# Schematic_Rev2.net
KiCad netlist of a schematic drawn in Altium Designer
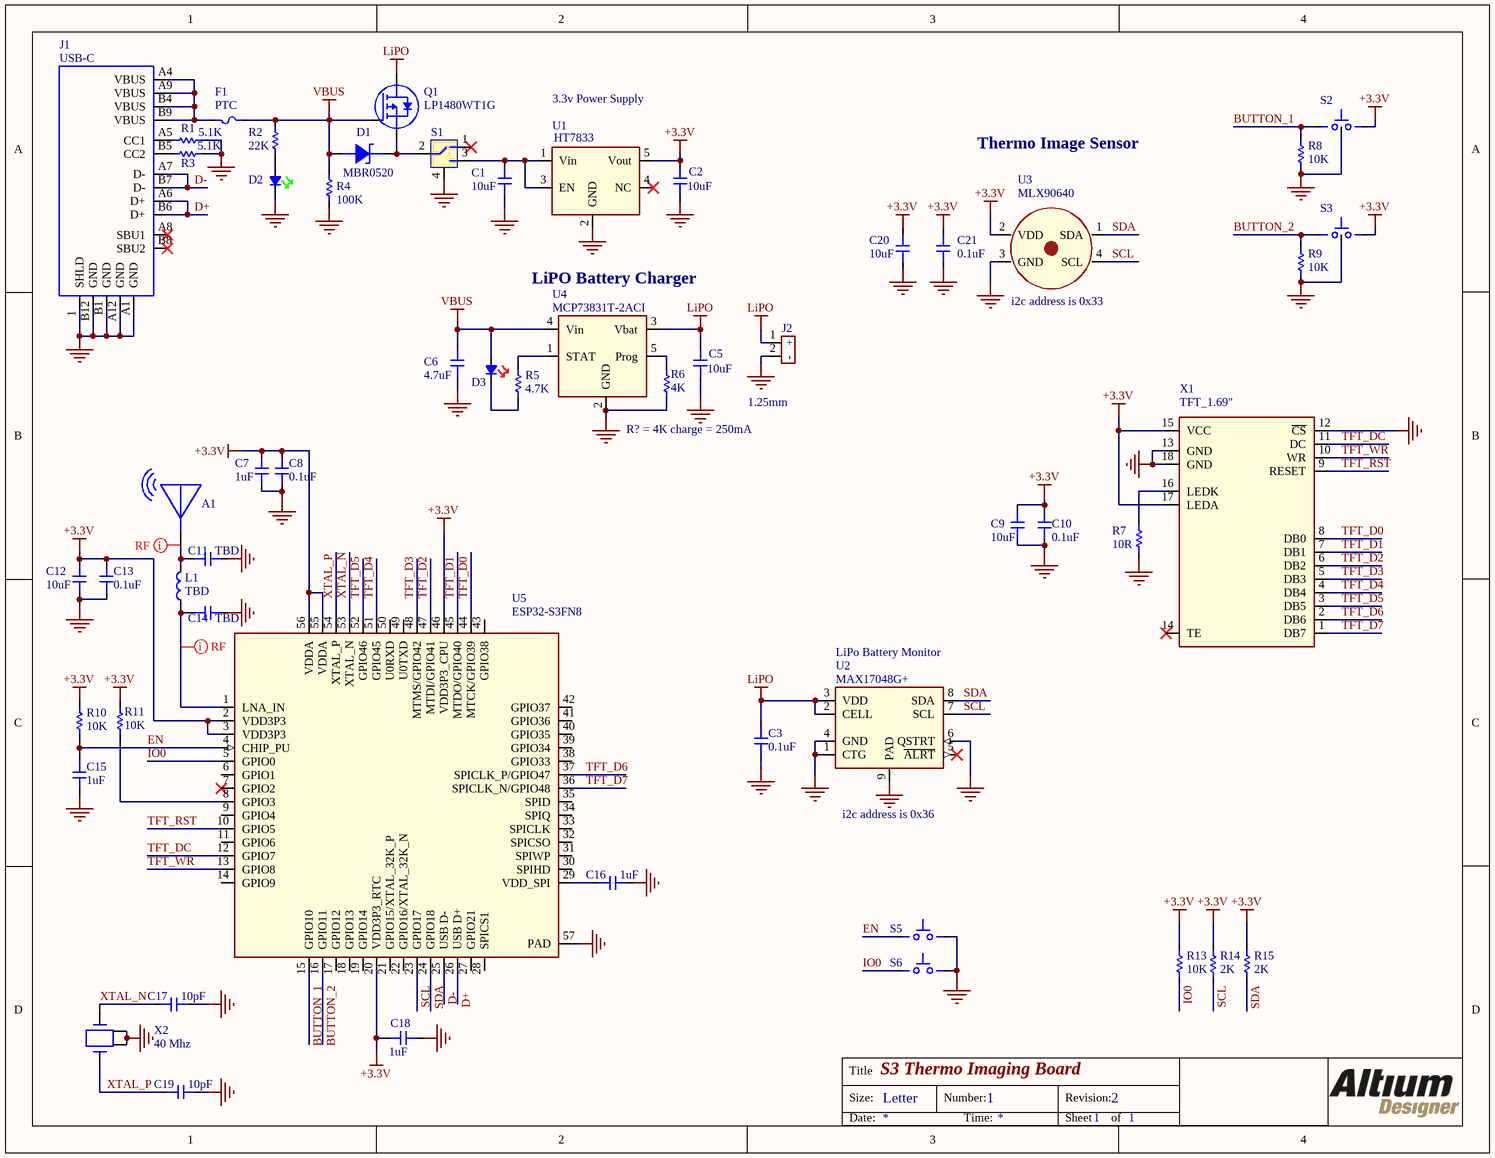
[diagram p0: Schematic_Rev2.SchDoc]

(export (version "E")
  (design (tool "Eeschema 10.0.6"))
  (components
    (comp (ref "A1")
      (value "ANT3216LL00R2400A")
      (footprint "ANT3216LL00R2400A")
      (description "Antenna Chip 2.4Gig")
      (fields (field (name "MANUFACTURER") "YAGEO"))
      (libsource (lib "MAR") (part "ANT3216LL00R2400A"))
    )
    (comp (ref "C1")
      (value "10uF")
      (footprint "CAPC2012X140N")
      (description "CAP 10uF 50V 0805")
      (libsource (lib "MAR") (part "CAP_0805"))
    )
    (comp (ref "C2")
      (value "10uF")
      (footprint "CAPC2012X140N")
      (description "CAP 10uF 50V 0805")
      (libsource (lib "MAR") (part "CAP_0805"))
    )
    (comp (ref "C3")
      (value "0.1uF")
      (footprint "CAPC1005X56N")
      (description "CAP 0.1uF 0402")
      (libsource (lib "MAR") (part "CAP_0402"))
    )
    (comp (ref "C5")
      (value "10uF")
      (footprint "CAPC2012X140N")
      (description "CAP 10uF 50V 0805")
      (libsource (lib "MAR") (part "CAP_0805"))
    )
    (comp (ref "C6")
      (value "4.7uF")
      (footprint "CAPC2012X140N")
      (description "CAP 4.7uF 0805")
      (libsource (lib "MAR") (part "CAP_0805"))
    )
    (comp (ref "C7")
      (value "1uF")
      (footprint "CAPC1608X09L")
      (description "CAP 1uF 0603")
      (libsource (lib "MAR") (part "CAP_0603"))
    )
    (comp (ref "C8")
      (value "0.1uF")
      (footprint "CAPC1608X09L")
      (description "CAP 0.1uF 0603")
      (libsource (lib "MAR") (part "CAP_0603"))
    )
    (comp (ref "C9")
      (value "10uF")
      (footprint "CAPC2012X140N")
      (description "CAP 10uF 0805")
      (libsource (lib "MAR") (part "CAP_0805"))
    )
    (comp (ref "C10")
      (value "0.1uF")
      (footprint "CAPC1608X09L")
      (description "CAP 0.1uF 0603")
      (libsource (lib "MAR") (part "CAP_0603"))
    )
    (comp (ref "C11")
      (value "TBD")
      (footprint "CAPC1005X56N")
      (description "CAP TBD 0402")
      (libsource (lib "MAR") (part "CAP_0402"))
    )
    (comp (ref "C12")
      (value "10uF")
      (footprint "CAPC2012X140N")
      (description "CAP 10uF 50V 0805")
      (libsource (lib "MAR") (part "CAP_0805"))
    )
    (comp (ref "C13")
      (value "0.1uF")
      (footprint "CAPC1005X56N")
      (description "CAP 0.1uF 0402")
      (libsource (lib "MAR") (part "CAP_0402"))
    )
    (comp (ref "C14")
      (value "TBD")
      (footprint "CAPC1005X56N")
      (description "CAP 0402")
      (libsource (lib "MAR") (part "CAP_0402"))
    )
    (comp (ref "C15")
      (value "1uF")
      (footprint "CAPC1005X56N")
      (description "CAP 1uF 0402")
      (libsource (lib "MAR") (part "CAP_0402"))
    )
    (comp (ref "C16")
      (value "1uF")
      (footprint "CAPC1005X56N")
      (description "CAP 1uF 0402")
      (libsource (lib "MAR") (part "CAP_0402"))
    )
    (comp (ref "C17")
      (value "10pF")
      (footprint "CAPC1005X56N")
      (description "CAP 10pF 0402")
      (libsource (lib "MAR") (part "CAP_0402"))
    )
    (comp (ref "C18")
      (value "1uF")
      (footprint "CAPC1608X09L")
      (description "CAP 1uF 0603")
      (libsource (lib "MAR") (part "CAP_0603"))
    )
    (comp (ref "C19")
      (value "10pF")
      (footprint "CAPC1005X56N")
      (description "CAP 10pF 0402")
      (libsource (lib "MAR") (part "CAP_0402"))
    )
    (comp (ref "C20")
      (value "10uF")
      (footprint "CAPC2012X140N")
      (description "CAP 10uF 50V 0805")
      (libsource (lib "MAR") (part "CAP_0805"))
    )
    (comp (ref "C21")
      (value "0.1uF")
      (footprint "CAPC1608X09L")
      (description "CAP 0.1uF 0603")
      (libsource (lib "MAR") (part "CAP_0603"))
    )
    (comp (ref "D1")
      (value "MBR0520")
      (footprint "SOD123")
      (description "DIODE SCHOTTKY 20V 500MA SOD-123")
      (fields (field (name "MANUFACTURER") "Micro") (field (name "PART_NUMBER") "C78746"))
      (libsource (lib "MAR") (part "MBR0520-TP"))
    )
    (comp (ref "D2")
      (value "Green Led")
      (footprint "LED1005X40N-Green")
      (description "LED Green 0402")
      (fields (field (name "PART_NUMBER") "C74338"))
      (libsource (lib "MAR") (part "LED_0402_SMALL_GREEN"))
    )
    (comp (ref "D3")
      (value "Red Led")
      (footprint "LED1005X40N-Red")
      (description "LED Red 0402")
      (fields (field (name "PART_NUMBER") "C364556") (field (name "MANUFACTURER") "Lite-On"))
      (libsource (lib "MAR") (part "LED_0402_SMALL_Red"))
    )
    (comp (ref "F1")
      (value "PTC")
      (footprint "RESC1608X06L (0603 FOOTPRINT)")
      (description "PTC FUSE 0.5mA hold, 1A trip 0603")
      (fields (field (name "MANUFACTURER") "JDT Fuse") (field (name "PART_NUMBER") "C2982257"))
      (libsource (lib "MAR") (part "PTC_FUSE_0603"))
    )
    (comp (ref "J1")
      (value "USB-C")
      (footprint "TYPE-C-31-M-12")
      (description "CONN RECPT USB-C")
      (fields (field (name "MANUFACTURER") "KHE") (field (name "PART_NUMBER") "C165948"))
      (libsource (lib "MAR") (part "USB-C"))
    )
    (comp (ref "J2")
      (value "1.5mm")
      (footprint "0530470260")
      (description "MIcro Conn 2POS 1.25mm Pitch Vertical")
      (fields (field (name "PART_NUMBER") "0530470260") (field (name "MANUFACTURER") "Molex"))
      (libsource (lib "MAR") (part "Molex_onn_2Pin_1.25mm_Vert"))
    )
    (comp (ref "L1")
      (value "TBD")
      (footprint "INDC1005X40L")
      (description "Inductor TBD")
      (libsource (lib "MAR") (part "Inductor"))
    )
    (comp (ref "Q1")
      (value "LP1480WT1G")
      (footprint "SC-70")
      (description "MOSFET P-CH 20V 1.4A SC-70")
      (fields (field (name "MANUFACTURER") "LRC") (field (name "PART_NUMBER") "C172434"))
      (libsource (lib "MAR") (part "LP1480WT1G"))
    )
    (comp (ref "R1")
      (value "5.1K")
      (footprint "RESC1005X40L (0402 FOOTPRINT)")
      (description "RES 5.1K 0402")
      (libsource (lib "MAR") (part "RES_0402"))
    )
    (comp (ref "R2")
      (value "22K")
      (footprint "RESC1005X40L (0402 FOOTPRINT)")
      (description "RES 22K 0402")
      (libsource (lib "MAR") (part "RES_0402"))
    )
    (comp (ref "R3")
      (value "5.1K")
      (footprint "RESC1005X40L (0402 FOOTPRINT)")
      (description "RES 5.1K 0402")
      (libsource (lib "MAR") (part "RES_0402"))
    )
    (comp (ref "R4")
      (value "100K")
      (footprint "RESC1005X40L (0402 FOOTPRINT)")
      (description "RES 100K 0402")
      (libsource (lib "MAR") (part "RES_0402"))
    )
    (comp (ref "R5")
      (value "4.7K")
      (footprint "RESC1005X40L (0402 FOOTPRINT)")
      (description "RES 4.7K 0402")
      (libsource (lib "MAR") (part "RES_0402"))
    )
    (comp (ref "R6")
      (value "4K")
      (footprint "RESC1005X40L (0402 FOOTPRINT)")
      (description "RES 4K 0402")
      (libsource (lib "MAR") (part "RES_0402"))
    )
    (comp (ref "R7")
      (value "10R")
      (footprint "RESC1005X40L (0402 FOOTPRINT)")
      (description "RES 10R 0402")
      (libsource (lib "MAR") (part "RES_0402"))
    )
    (comp (ref "R8")
      (value "10K")
      (footprint "RESC1005X40L (0402 FOOTPRINT)")
      (description "RES 10K 0402")
      (libsource (lib "MAR") (part "RES_0402"))
    )
    (comp (ref "R9")
      (value "10K")
      (footprint "RESC1005X40L (0402 FOOTPRINT)")
      (description "RES 10K 0402")
      (libsource (lib "MAR") (part "RES_0402"))
    )
    (comp (ref "R10")
      (value "10K")
      (footprint "RESC1005X40L (0402 FOOTPRINT)")
      (description "RES 10K 0402")
      (libsource (lib "MAR") (part "RES_0402"))
    )
    (comp (ref "R11")
      (value "10K")
      (footprint "RESC1005X40L (0402 FOOTPRINT)")
      (description "RES 10K 0402")
      (libsource (lib "MAR") (part "RES_0402"))
    )
    (comp (ref "R13")
      (value "10K")
      (footprint "RESC1005X40L (0402 FOOTPRINT)")
      (description "RES 10K 0402")
      (libsource (lib "MAR") (part "RES_0402"))
    )
    (comp (ref "R14")
      (value "2K")
      (footprint "RESC1005X40L (0402 FOOTPRINT)")
      (description "RES 2K 0402")
      (libsource (lib "MAR") (part "RES_0402"))
    )
    (comp (ref "R15")
      (value "2K")
      (footprint "RESC1005X40L (0402 FOOTPRINT)")
      (description "RES 2K 0402")
      (libsource (lib "MAR") (part "RES_0402"))
    )
    (comp (ref "S1")
      (value "SWITCH SLIDE")
      (footprint "K3-1296S-E1")
      (description "SWITCH SLIDE SMD")
      (fields (field (name "MANUFACTURER") "Korean Hroparts Elec") (field (name "PART_NUMBER") "K3-1296S-E1"))
      (libsource (lib "MAR") (part "K3-1296S-E1"))
    )
    (comp (ref "S2")
      (value "Push")
      (footprint "1TS003B-1600-3500A-CT")
      (description "SWITCH TACTILE R/A MICRO")
      (fields (field (name "PART_NUMBER") "C255808") (field (name "MANUFACTURER") "HYP"))
      (libsource (lib "MAR") (part "SWITCH TACTILE R/A_MICRO"))
    )
    (comp (ref "S3")
      (value "Push")
      (footprint "1TS003B-1600-3500A-CT")
      (description "SWITCH TACTILE R/A MICRO")
      (fields (field (name "PART_NUMBER") "C255808") (field (name "MANUFACTURER") "HYP"))
      (libsource (lib "MAR") (part "SWITCH TACTILE R/A_MICRO"))
    )
    (comp (ref "S5")
      (value "~")
      (footprint "TL1015AF160QG")
      (description "SWITCH MOMENTARY")
      (fields (field (name "PART_NUMBER") "TL1015AF160QG"))
      (libsource (lib "MAR") (part "TL1015AF160QG"))
    )
    (comp (ref "S6")
      (value "~")
      (footprint "TL1015AF160QG")
      (description "SWITCH MOMENTARY")
      (fields (field (name "PART_NUMBER") "TL1015AF160QG"))
      (libsource (lib "MAR") (part "TL1015AF160QG"))
    )
    (comp (ref "U1")
      (value "HT7833")
      (footprint "SOT95P280X144-5N")
      (description "IC LDO 3.3V 0.5A SOT23-5")
      (fields (field (name "MANUFACTURER") "Holtek") (field (name "PART_NUMBER") "C164106"))
      (libsource (lib "MAR") (part "HT7833"))
    )
    (comp (ref "U2")
      (value "MAX17048G+")
      (footprint "DFN-8_Smaller")
      (description "IC BATT MON LI-ION 1CELL 8TDFN")
      (fields (field (name "MANUFACTURER") "Analog Devices") (field (name "PART_NUMBER") "MAX17048G+"))
      (libsource (lib "MAR") (part "MAX17048G+"))
    )
    (comp (ref "U3")
      (value "MLX90640")
      (footprint "MLX90640ESF")
      (description "Thermal Image Sensor TO-39")
      (fields (field (name "MANUFACTURER") "Melexis") (field (name "PART_NUMBER") "MLX90640ESF-BAB-000-TU"))
      (libsource (lib "MAR") (part "MLX90640ESF-BAB-000-TU"))
    )
    (comp (ref "U4")
      (value "MCP73831T-2ACI")
      (footprint "SOT95P280X144-5N")
      (description "Charger IC Lithium-Ion/Polymer SOT23-5")
      (fields (field (name "MANUFACTURER") "Microchip") (field (name "PART_NUMBER") "MCP73831T-2ACI/OT"))
      (libsource (lib "MAR") (part "MCP73831T-2ACI/OT"))
    )
    (comp (ref "U5")
      (value "ESP32-S3FN8")
      (footprint "QFN56_0.4mm pitch - Rev2")
      (description "WIFI/Bluetooth, 8M PSRAM, QFN-56 7x7")
      (fields (field (name "MANUFACTURER") "Espressif"))
      (libsource (lib "MAR") (part "ESP32-S3"))
    )
    (comp (ref "X1")
      (value "TFT_1.69\"")
      (footprint "TFT_GLASS 1.69 INCH 8-BIT")
      (description "1.69 INCH TFT 8-BIT PARALLEL BUS")
      (fields (field (name "PART_NUMBER") "ER-TFT1.69-1") (field (name "MANUFACTURER") "BuyDisplay"))
      (libsource (lib "MAR") (part "TFT_GLASS 1.69 INCH COLOR 8-BIT"))
    )
    (comp (ref "X2")
      (value "40 Mhz")
      (footprint "OSC20X16")
      (description "CRYSTAL 40MHZ 10PF SMD")
      (fields (field (name "PART_NUMBER") "ECS-400-10-37B2-CKM") (field (name "MANUFACTURER") "ECS"))
      (libsource (lib "MAR") (part "40Mhz"))
    )
  )
  (nets
    (net (code "1") (name "+3.3V") (class "Default")
      (node (ref "C10") (pin "1") (pintype "passive"))
      (node (ref "C12") (pin "1") (pintype "passive"))
      (node (ref "C13") (pin "1") (pintype "passive"))
      (node (ref "C18") (pin "2") (pintype "passive"))
      (node (ref "C2") (pin "1") (pintype "passive"))
      (node (ref "C20") (pin "1") (pintype "passive"))
      (node (ref "C21") (pin "1") (pintype "passive"))
      (node (ref "C7") (pin "1") (pintype "passive"))
      (node (ref "C8") (pin "1") (pintype "passive"))
      (node (ref "C9") (pin "1") (pintype "passive"))
      (node (ref "R10") (pin "2") (pintype "passive"))
      (node (ref "R11") (pin "1") (pintype "passive"))
      (node (ref "R13") (pin "1") (pintype "passive"))
      (node (ref "R14") (pin "1") (pintype "passive"))
      (node (ref "R15") (pin "1") (pintype "passive"))
      (node (ref "S2") (pin "2") (pinfunction "B_2") (pintype "passive"))
      (node (ref "S3") (pin "2") (pinfunction "B_2") (pintype "passive"))
      (node (ref "U1") (pin "5") (pinfunction "Vout_5") (pintype "passive"))
      (node (ref "U3") (pin "2") (pinfunction "VDD_2") (pintype "power_in"))
      (node (ref "U5") (pin "2") (pinfunction "VDD3P3_2") (pintype "power_in"))
      (node (ref "U5") (pin "20") (pinfunction "VDD3P3_RTC_20") (pintype "power_in"))
      (node (ref "U5") (pin "3") (pinfunction "VDD3P3_3") (pintype "power_in"))
      (node (ref "U5") (pin "46") (pinfunction "VDD3P3_CPU_46") (pintype "power_in"))
      (node (ref "U5") (pin "55") (pinfunction "VDDA_55") (pintype "power_in"))
      (node (ref "U5") (pin "56") (pinfunction "VDDA_56") (pintype "power_in"))
      (node (ref "X1") (pin "15") (pinfunction "VCC_15") (pintype "power_in"))
      (node (ref "X1") (pin "17") (pinfunction "LEDA_17") (pintype "passive"))
    )
    (net (code "2") (name "/BUTTON_1") (class "Default")
      (node (ref "R8") (pin "2") (pintype "passive"))
      (node (ref "S2") (pin "1") (pinfunction "A_1") (pintype "passive"))
      (node (ref "U5") (pin "15") (pinfunction "GPIO10_15") (pintype "passive"))
    )
    (net (code "3") (name "/BUTTON_2") (class "Default")
      (node (ref "R9") (pin "2") (pintype "passive"))
      (node (ref "S3") (pin "1") (pinfunction "A_1") (pintype "passive"))
      (node (ref "U5") (pin "16") (pinfunction "GPIO11_16") (pintype "passive"))
    )
    (net (code "4") (name "/D+") (class "Default")
      (node (ref "J1") (pin "A6") (pinfunction "D+_A6") (pintype "power_in"))
      (node (ref "J1") (pin "B6") (pinfunction "D+_B6") (pintype "power_in"))
      (node (ref "U5") (pin "26") (pinfunction "USB_D+_26") (pintype "passive"))
    )
    (net (code "5") (name "/D-") (class "Default")
      (node (ref "J1") (pin "A7") (pinfunction "D-_A7") (pintype "power_in"))
      (node (ref "J1") (pin "B7") (pinfunction "D-_B7") (pintype "power_in"))
      (node (ref "U5") (pin "25") (pinfunction "USB_D-_25") (pintype "passive"))
    )
    (net (code "6") (name "/EN") (class "Default")
      (node (ref "C15") (pin "1") (pintype "passive"))
      (node (ref "R10") (pin "1") (pintype "passive"))
      (node (ref "S5") (pin "1") (pinfunction "A_1") (pintype "passive"))
      (node (ref "U5") (pin "4") (pinfunction "CHIP_PU_4") (pintype "input"))
    )
    (net (code "7") (name "/IO0") (class "Default")
      (node (ref "R13") (pin "2") (pintype "passive"))
      (node (ref "S6") (pin "1") (pinfunction "A_1") (pintype "passive"))
      (node (ref "U5") (pin "5") (pinfunction "GPIO0_5") (pintype "passive"))
    )
    (net (code "8") (name "/SCL") (class "Default")
      (node (ref "R14") (pin "2") (pintype "passive"))
      (node (ref "U2") (pin "7") (pinfunction "SCL_7") (pintype "passive"))
      (node (ref "U3") (pin "4") (pinfunction "SCL_4") (pintype "passive"))
      (node (ref "U5") (pin "23") (pinfunction "GPIO17_23") (pintype "passive"))
    )
    (net (code "9") (name "/SDA") (class "Default")
      (node (ref "R15") (pin "2") (pintype "passive"))
      (node (ref "U2") (pin "8") (pinfunction "SDA_8") (pintype "passive"))
      (node (ref "U3") (pin "1") (pinfunction "SDA_1") (pintype "passive"))
      (node (ref "U5") (pin "24") (pinfunction "GPIO18_24") (pintype "passive"))
    )
    (net (code "10") (name "/TFT_D0") (class "Default")
      (node (ref "U5") (pin "44") (pinfunction "MTCK/GPIO39_44") (pintype "passive"))
      (node (ref "X1") (pin "8") (pinfunction "DB0_8") (pintype "passive"))
    )
    (net (code "11") (name "/TFT_D1") (class "Default")
      (node (ref "U5") (pin "45") (pinfunction "MTDO/GPIO40_45") (pintype "passive"))
      (node (ref "X1") (pin "7") (pinfunction "DB1_7") (pintype "passive"))
    )
    (net (code "12") (name "/TFT_D2") (class "Default")
      (node (ref "U5") (pin "47") (pinfunction "MTDI/GPIO41_47") (pintype "passive"))
      (node (ref "X1") (pin "6") (pinfunction "DB2_6") (pintype "passive"))
    )
    (net (code "13") (name "/TFT_D3") (class "Default")
      (node (ref "U5") (pin "48") (pinfunction "MTMS/GPIO42_48") (pintype "passive"))
      (node (ref "X1") (pin "5") (pinfunction "DB3_5") (pintype "passive"))
    )
    (net (code "14") (name "/TFT_D4") (class "Default")
      (node (ref "U5") (pin "51") (pinfunction "GPIO45_51") (pintype "passive"))
      (node (ref "X1") (pin "4") (pinfunction "DB4_4") (pintype "passive"))
    )
    (net (code "15") (name "/TFT_D5") (class "Default")
      (node (ref "U5") (pin "52") (pinfunction "GPIO46_52") (pintype "passive"))
      (node (ref "X1") (pin "3") (pinfunction "DB5_3") (pintype "passive"))
    )
    (net (code "16") (name "/TFT_D6") (class "Default")
      (node (ref "U5") (pin "37") (pinfunction "SPICLK_P/GPIO47_37") (pintype "passive"))
      (node (ref "X1") (pin "2") (pinfunction "DB6_2") (pintype "passive"))
    )
    (net (code "17") (name "/TFT_D7") (class "Default")
      (node (ref "U5") (pin "36") (pinfunction "SPICLK_N/GPIO48_36") (pintype "passive"))
      (node (ref "X1") (pin "1") (pinfunction "DB7_1") (pintype "passive"))
    )
    (net (code "18") (name "/TFT_DC") (class "Default")
      (node (ref "U5") (pin "12") (pinfunction "GPIO7_12") (pintype "passive"))
      (node (ref "X1") (pin "11") (pinfunction "DC_11") (pintype "passive"))
    )
    (net (code "19") (name "/TFT_RST") (class "Default")
      (node (ref "U5") (pin "10") (pinfunction "GPIO5_10") (pintype "passive"))
      (node (ref "X1") (pin "9") (pinfunction "RESET_9") (pintype "passive"))
    )
    (net (code "20") (name "/TFT_WR") (class "Default")
      (node (ref "U5") (pin "13") (pinfunction "GPIO8_13") (pintype "passive"))
      (node (ref "X1") (pin "10") (pinfunction "WR_10") (pintype "passive"))
    )
    (net (code "21") (name "/XTAL_N") (class "Default")
      (node (ref "C17") (pin "1") (pintype "passive"))
      (node (ref "U5") (pin "53") (pinfunction "XTAL_N_53") (pintype "passive"))
      (node (ref "X2") (pin "3") (pinfunction "3_3") (pintype "passive"))
    )
    (net (code "22") (name "/XTAL_P") (class "Default")
      (node (ref "C19") (pin "1") (pintype "passive"))
      (node (ref "U5") (pin "54") (pinfunction "XTAL_P_54") (pintype "passive"))
      (node (ref "X2") (pin "1") (pinfunction "1_1") (pintype "passive"))
    )
    (net (code "23") (name "GND") (class "Default")
      (node (ref "C1") (pin "2") (pintype "passive"))
      (node (ref "C10") (pin "2") (pintype "passive"))
      (node (ref "C11") (pin "2") (pintype "passive"))
      (node (ref "C12") (pin "2") (pintype "passive"))
      (node (ref "C13") (pin "2") (pintype "passive"))
      (node (ref "C14") (pin "2") (pintype "passive"))
      (node (ref "C15") (pin "2") (pintype "passive"))
      (node (ref "C16") (pin "2") (pintype "passive"))
      (node (ref "C17") (pin "2") (pintype "passive"))
      (node (ref "C18") (pin "1") (pintype "passive"))
      (node (ref "C19") (pin "2") (pintype "passive"))
      (node (ref "C2") (pin "2") (pintype "passive"))
      (node (ref "C20") (pin "2") (pintype "passive"))
      (node (ref "C21") (pin "2") (pintype "passive"))
      (node (ref "C3") (pin "2") (pintype "passive"))
      (node (ref "C5") (pin "2") (pintype "passive"))
      (node (ref "C6") (pin "2") (pintype "passive"))
      (node (ref "C7") (pin "2") (pintype "passive"))
      (node (ref "C8") (pin "2") (pintype "passive"))
      (node (ref "C9") (pin "2") (pintype "passive"))
      (node (ref "D2") (pin "1") (pintype "passive"))
      (node (ref "J1") (pin "1") (pinfunction "SHLD_1") (pintype "power_in"))
      (node (ref "J1") (pin "A1") (pinfunction "GND_A1") (pintype "power_in"))
      (node (ref "J1") (pin "A12") (pinfunction "GND_A12") (pintype "power_in"))
      (node (ref "J1") (pin "B1") (pinfunction "GND_B1") (pintype "power_in"))
      (node (ref "J1") (pin "B12") (pinfunction "GND_B12") (pintype "passive"))
      (node (ref "J2") (pin "2") (pintype "passive"))
      (node (ref "R1") (pin "1") (pintype "passive"))
      (node (ref "R3") (pin "1") (pintype "passive"))
      (node (ref "R4") (pin "2") (pintype "passive"))
      (node (ref "R6") (pin "1") (pintype "passive"))
      (node (ref "R7") (pin "2") (pintype "passive"))
      (node (ref "R8") (pin "1") (pintype "passive"))
      (node (ref "R9") (pin "1") (pintype "passive"))
      (node (ref "S1") (pin "4") (pinfunction "4_4") (pintype "passive"))
      (node (ref "S2") (pin "3") (pinfunction "3_3") (pintype "passive"))
      (node (ref "S3") (pin "3") (pinfunction "3_3") (pintype "passive"))
      (node (ref "S5") (pin "2") (pinfunction "B_2") (pintype "passive"))
      (node (ref "S6") (pin "2") (pinfunction "B_2") (pintype "passive"))
      (node (ref "U1") (pin "2") (pinfunction "GND_2") (pintype "power_in"))
      (node (ref "U2") (pin "1") (pinfunction "CTG_1") (pintype "power_in"))
      (node (ref "U2") (pin "4") (pinfunction "GND_4") (pintype "power_in"))
      (node (ref "U2") (pin "6") (pinfunction "QSTRT_6") (pintype "input"))
      (node (ref "U2") (pin "9") (pinfunction "PAD_9") (pintype "power_in"))
      (node (ref "U3") (pin "3") (pinfunction "GND_3") (pintype "power_in"))
      (node (ref "U4") (pin "2") (pinfunction "GND_2") (pintype "power_in"))
      (node (ref "U5") (pin "57") (pinfunction "PAD_57") (pintype "power_in"))
      (node (ref "X1") (pin "12") (pinfunction "~{CS}_12") (pintype "passive"))
      (node (ref "X1") (pin "13") (pinfunction "GND_13") (pintype "power_in"))
      (node (ref "X1") (pin "18") (pinfunction "GND_18") (pintype "power_in"))
      (node (ref "X2") (pin "2") (pinfunction "2_2") (pintype "power_in"))
      (node (ref "X2") (pin "4") (pinfunction "4_4") (pintype "power_in"))
    )
    (net (code "24") (name "LiPO") (class "Default")
      (node (ref "C3") (pin "1") (pintype "passive"))
      (node (ref "C5") (pin "1") (pintype "passive"))
      (node (ref "J2") (pin "1") (pintype "passive"))
      (node (ref "Q1") (pin "3") (pinfunction "D_3") (pintype "passive"))
      (node (ref "U2") (pin "2") (pinfunction "CELL_2") (pintype "power_in"))
      (node (ref "U2") (pin "3") (pinfunction "VDD_3") (pintype "power_in"))
      (node (ref "U4") (pin "3") (pinfunction "Vbat_3") (pintype "passive"))
    )
    (net (code "25") (name "Net-(A1-Pad1)") (class "Default")
      (node (ref "A1") (pin "1") (pintype "passive"))
      (node (ref "C11") (pin "1") (pintype "passive"))
      (node (ref "L1") (pin "1") (pinfunction "1_1") (pintype "passive"))
    )
    (net (code "26") (name "Net-(D1-Cathode)") (class "Default")
      (node (ref "D1") (pin "1") (pinfunction "Cathode_1") (pintype "passive"))
      (node (ref "Q1") (pin "2") (pinfunction "S_2") (pintype "passive"))
      (node (ref "S1") (pin "2") (pinfunction "2_2") (pintype "passive"))
    )
    (net (code "27") (name "Net-(D2-Pad2)") (class "Default")
      (node (ref "D2") (pin "2") (pintype "passive"))
      (node (ref "R2") (pin "1") (pintype "passive"))
    )
    (net (code "28") (name "Net-(D3-Pad1)") (class "Default")
      (node (ref "D3") (pin "1") (pintype "passive"))
      (node (ref "R5") (pin "1") (pintype "passive"))
    )
    (net (code "29") (name "Net-(F1-Pad2)") (class "Default")
      (node (ref "F1") (pin "2") (pintype "passive"))
      (node (ref "J1") (pin "A4") (pinfunction "VBUS_A4") (pintype "passive"))
      (node (ref "J1") (pin "A9") (pinfunction "VBUS_A9") (pintype "power_in"))
      (node (ref "J1") (pin "B4") (pinfunction "VBUS_B4") (pintype "power_in"))
      (node (ref "J1") (pin "B9") (pinfunction "VBUS_B9") (pintype "passive"))
    )
    (net (code "30") (name "Net-(J1-CC1)") (class "Default")
      (node (ref "J1") (pin "A5") (pinfunction "CC1_A5") (pintype "power_in"))
      (node (ref "R1") (pin "2") (pintype "passive"))
    )
    (net (code "31") (name "Net-(J1-CC2)") (class "Default")
      (node (ref "J1") (pin "B5") (pinfunction "CC2_B5") (pintype "power_in"))
      (node (ref "R3") (pin "2") (pintype "passive"))
    )
    (net (code "32") (name "Net-(U1-EN)") (class "Default")
      (node (ref "C1") (pin "1") (pintype "passive"))
      (node (ref "S1") (pin "3") (pinfunction "3_3") (pintype "passive"))
      (node (ref "U1") (pin "1") (pinfunction "Vin_1") (pintype "passive"))
      (node (ref "U1") (pin "3") (pinfunction "EN_3") (pintype "passive"))
    )
    (net (code "33") (name "Net-(U4-Prog)") (class "Default")
      (node (ref "R6") (pin "2") (pintype "passive"))
      (node (ref "U4") (pin "5") (pinfunction "Prog_5") (pintype "passive"))
    )
    (net (code "34") (name "Net-(U4-STAT)") (class "Default")
      (node (ref "R5") (pin "2") (pintype "passive"))
      (node (ref "U4") (pin "1") (pinfunction "STAT_1") (pintype "passive"))
    )
    (net (code "35") (name "Net-(U5-GPIO3)") (class "Default")
      (node (ref "R11") (pin "2") (pintype "passive"))
      (node (ref "U5") (pin "8") (pinfunction "GPIO3_8") (pintype "passive"))
    )
    (net (code "36") (name "Net-(U5-LNA_IN)") (class "Default")
      (node (ref "C14") (pin "1") (pintype "passive"))
      (node (ref "L1") (pin "2") (pinfunction "2_2") (pintype "passive"))
      (node (ref "U5") (pin "1") (pinfunction "LNA_IN_1") (pintype "passive"))
    )
    (net (code "37") (name "Net-(U5-VDD_SPI)") (class "Default")
      (node (ref "C16") (pin "1") (pintype "passive"))
      (node (ref "U5") (pin "29") (pinfunction "VDD_SPI_29") (pintype "power_in"))
    )
    (net (code "38") (name "Net-(X1-LEDK)") (class "Default")
      (node (ref "R7") (pin "1") (pintype "passive"))
      (node (ref "X1") (pin "16") (pinfunction "LEDK_16") (pintype "passive"))
    )
    (net (code "39") (name "VBUS") (class "Default")
      (node (ref "C6") (pin "1") (pintype "passive"))
      (node (ref "D1") (pin "2") (pinfunction "Annode_2") (pintype "passive"))
      (node (ref "D3") (pin "2") (pintype "passive"))
      (node (ref "F1") (pin "1") (pintype "passive"))
      (node (ref "Q1") (pin "1") (pinfunction "G_1") (pintype "passive"))
      (node (ref "R2") (pin "2") (pintype "passive"))
      (node (ref "R4") (pin "1") (pintype "passive"))
      (node (ref "U4") (pin "4") (pinfunction "Vin_4") (pintype "passive"))
    )
    (net (code "40") (name "unconnected-(J1-SBU1-PadA8)") (class "Default")
      (node (ref "J1") (pin "A8") (pinfunction "SBU1_A8") (pintype "power_in+no_connect"))
    )
    (net (code "41") (name "unconnected-(J1-SBU2-PadB8)") (class "Default")
      (node (ref "J1") (pin "B8") (pinfunction "SBU2_B8") (pintype "power_in+no_connect"))
    )
    (net (code "42") (name "unconnected-(S1-Pad1)") (class "Default")
      (node (ref "S1") (pin "1") (pinfunction "1_1") (pintype "passive+no_connect"))
    )
    (net (code "43") (name "unconnected-(U1-NC-Pad4)") (class "Default")
      (node (ref "U1") (pin "4") (pinfunction "NC_4") (pintype "passive+no_connect"))
    )
    (net (code "44") (name "unconnected-(U2-~{ALRT}-Pad5)") (class "Default")
      (node (ref "U2") (pin "5") (pinfunction "~{ALRT}_5") (pintype "output+no_connect"))
    )
    (net (code "45") (name "unconnected-(U5-GPIO1-Pad6)") (class "Default")
      (node (ref "U5") (pin "6") (pinfunction "GPIO1_6") (pintype "passive"))
    )
    (net (code "46") (name "unconnected-(U5-GPIO2-Pad7)") (class "Default")
      (node (ref "U5") (pin "7") (pinfunction "GPIO2_7") (pintype "passive+no_connect"))
    )
    (net (code "47") (name "unconnected-(U5-GPIO4-Pad9)") (class "Default")
      (node (ref "U5") (pin "9") (pinfunction "GPIO4_9") (pintype "passive"))
    )
    (net (code "48") (name "unconnected-(U5-GPIO6-Pad11)") (class "Default")
      (node (ref "U5") (pin "11") (pinfunction "GPIO6_11") (pintype "passive"))
    )
    (net (code "49") (name "unconnected-(U5-GPIO9-Pad14)") (class "Default")
      (node (ref "U5") (pin "14") (pinfunction "GPIO9_14") (pintype "passive"))
    )
    (net (code "50") (name "unconnected-(U5-GPIO12-Pad17)") (class "Default")
      (node (ref "U5") (pin "17") (pinfunction "GPIO12_17") (pintype "passive"))
    )
    (net (code "51") (name "unconnected-(U5-GPIO13-Pad18)") (class "Default")
      (node (ref "U5") (pin "18") (pinfunction "GPIO13_18") (pintype "passive"))
    )
    (net (code "52") (name "unconnected-(U5-GPIO14-Pad19)") (class "Default")
      (node (ref "U5") (pin "19") (pinfunction "GPIO14_19") (pintype "passive"))
    )
    (net (code "53") (name "unconnected-(U5-GPIO15{slash}XTAL_32K_P-Pad21)") (class "Default")
      (node (ref "U5") (pin "21") (pinfunction "GPIO15/XTAL_32K_P_21") (pintype "passive"))
    )
    (net (code "54") (name "unconnected-(U5-GPIO16{slash}XTAL_32K_N-Pad22)") (class "Default")
      (node (ref "U5") (pin "22") (pinfunction "GPIO16/XTAL_32K_N_22") (pintype "passive"))
    )
    (net (code "55") (name "unconnected-(U5-GPIO21-Pad27)") (class "Default")
      (node (ref "U5") (pin "27") (pinfunction "GPIO21_27") (pintype "passive"))
    )
    (net (code "56") (name "unconnected-(U5-GPIO33-Pad38)") (class "Default")
      (node (ref "U5") (pin "38") (pinfunction "GPIO33_38") (pintype "passive"))
    )
    (net (code "57") (name "unconnected-(U5-GPIO34-Pad39)") (class "Default")
      (node (ref "U5") (pin "39") (pinfunction "GPIO34_39") (pintype "passive"))
    )
    (net (code "58") (name "unconnected-(U5-GPIO35-Pad40)") (class "Default")
      (node (ref "U5") (pin "40") (pinfunction "GPIO35_40") (pintype "passive"))
    )
    (net (code "59") (name "unconnected-(U5-GPIO36-Pad41)") (class "Default")
      (node (ref "U5") (pin "41") (pinfunction "GPIO36_41") (pintype "passive"))
    )
    (net (code "60") (name "unconnected-(U5-GPIO37-Pad42)") (class "Default")
      (node (ref "U5") (pin "42") (pinfunction "GPIO37_42") (pintype "passive"))
    )
    (net (code "61") (name "unconnected-(U5-GPIO38-Pad43)") (class "Default")
      (node (ref "U5") (pin "43") (pinfunction "GPIO38_43") (pintype "passive"))
    )
    (net (code "62") (name "unconnected-(U5-SPICLK-Pad33)") (class "Default")
      (node (ref "U5") (pin "33") (pinfunction "SPICLK_33") (pintype "passive"))
    )
    (net (code "63") (name "unconnected-(U5-SPICS1-Pad28)") (class "Default")
      (node (ref "U5") (pin "28") (pinfunction "SPICS1_28") (pintype "passive"))
    )
    (net (code "64") (name "unconnected-(U5-SPICSO-Pad32)") (class "Default")
      (node (ref "U5") (pin "32") (pinfunction "SPICSO_32") (pintype "passive"))
    )
    (net (code "65") (name "unconnected-(U5-SPID-Pad35)") (class "Default")
      (node (ref "U5") (pin "35") (pinfunction "SPID_35") (pintype "passive"))
    )
    (net (code "66") (name "unconnected-(U5-SPIHD-Pad30)") (class "Default")
      (node (ref "U5") (pin "30") (pinfunction "SPIHD_30") (pintype "passive"))
    )
    (net (code "67") (name "unconnected-(U5-SPIQ-Pad34)") (class "Default")
      (node (ref "U5") (pin "34") (pinfunction "SPIQ_34") (pintype "passive"))
    )
    (net (code "68") (name "unconnected-(U5-SPIWP-Pad31)") (class "Default")
      (node (ref "U5") (pin "31") (pinfunction "SPIWP_31") (pintype "passive"))
    )
    (net (code "69") (name "unconnected-(U5-U0RXD-Pad50)") (class "Default")
      (node (ref "U5") (pin "50") (pinfunction "U0RXD_50") (pintype "passive"))
    )
    (net (code "70") (name "unconnected-(U5-U0TXD-Pad49)") (class "Default")
      (node (ref "U5") (pin "49") (pinfunction "U0TXD_49") (pintype "passive"))
    )
    (net (code "71") (name "unconnected-(X1-TE-Pad14)") (class "Default")
      (node (ref "X1") (pin "14") (pinfunction "TE_14") (pintype "passive+no_connect"))
    )
  )
)
